# Mother_Board.net
KiCad netlist of a schematic drawn in EAGLE
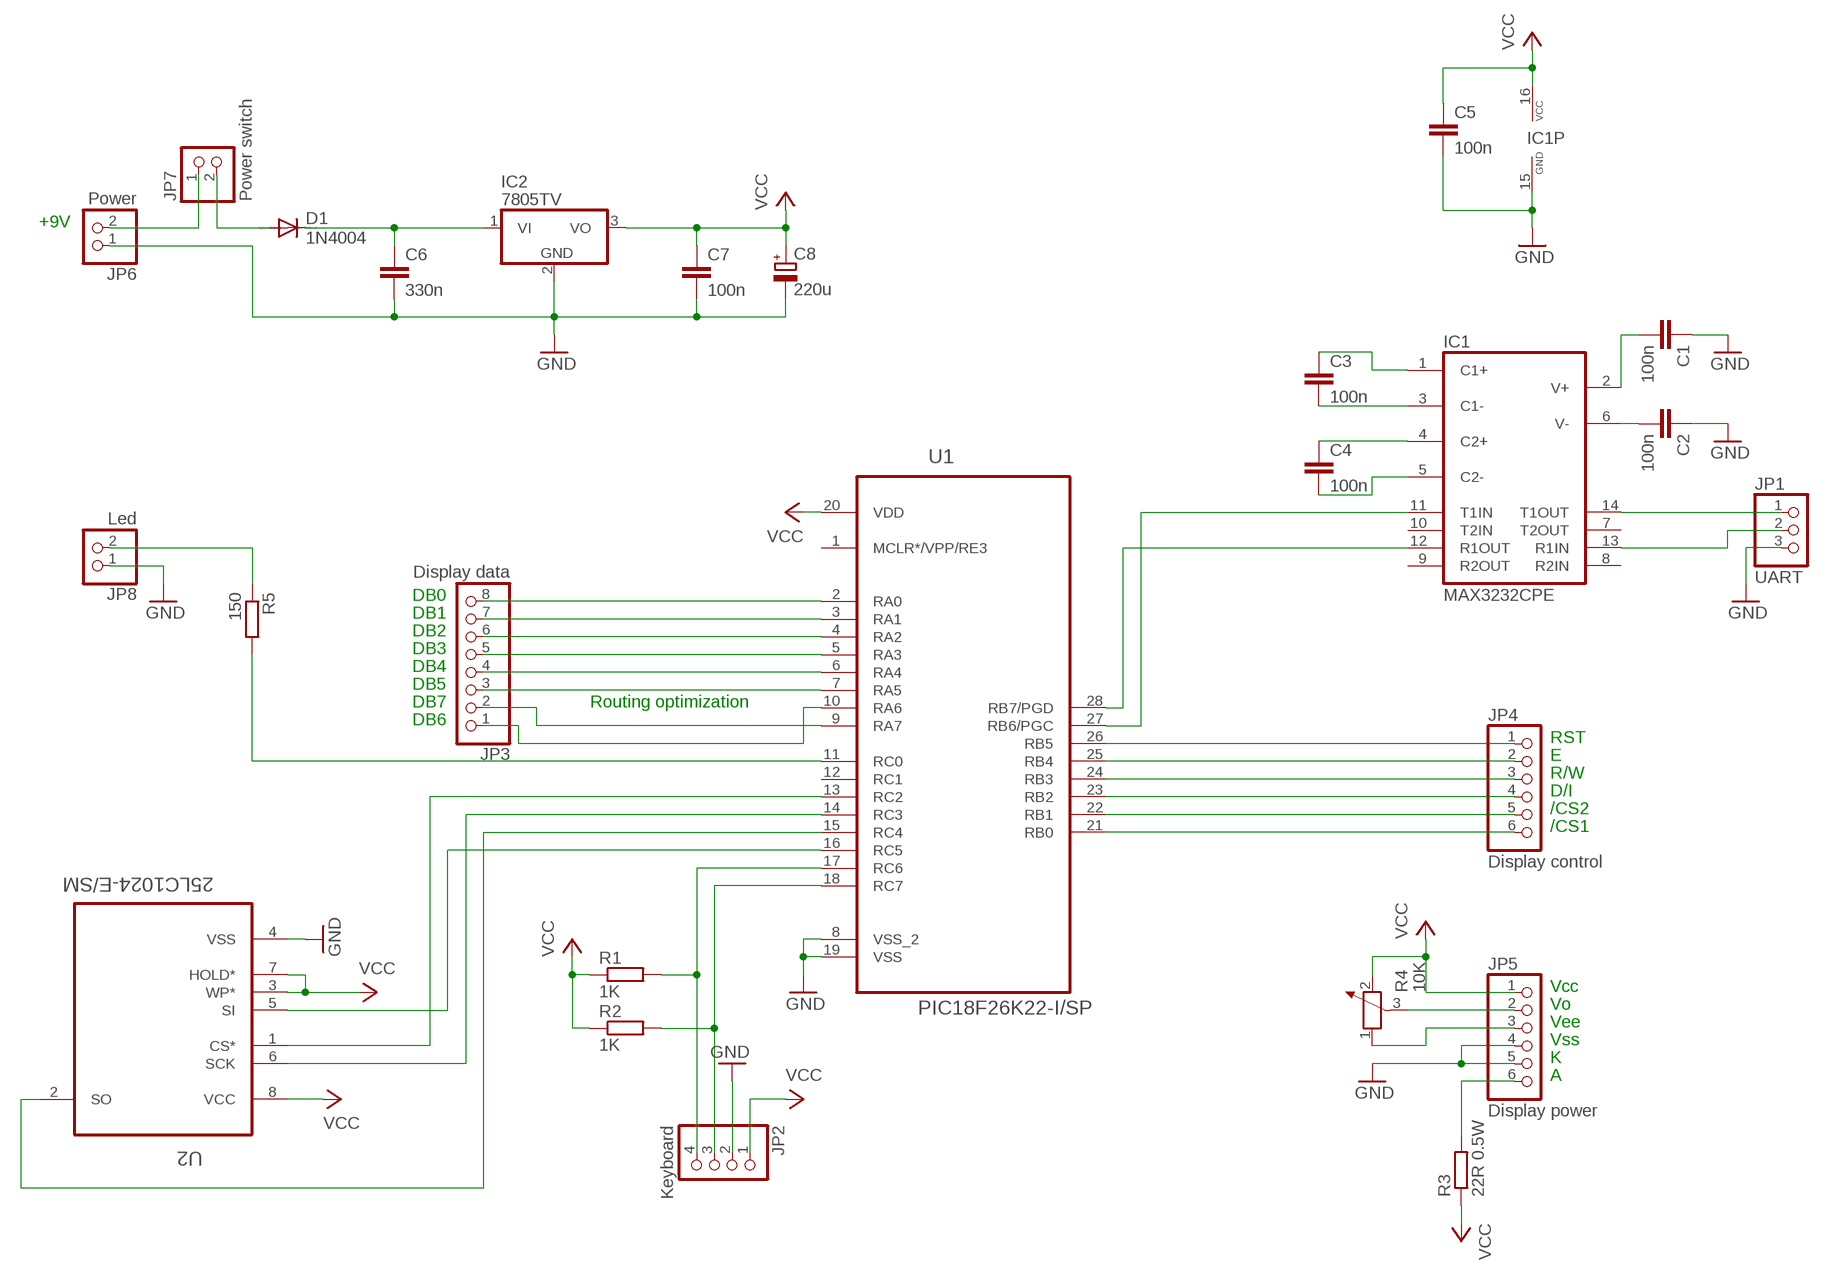
[diagram p0: schematic, sheet 1]

(export (version "E")
  (design (tool "Eeschema 10.0.6"))
  (components
    (comp (ref "C1")
      (value "100n")
      (footprint "eagle-import:C025-030X050")
      (libsource (lib "eagle-import") (part "C-EU025-030X050"))
    )
    (comp (ref "C2")
      (value "100n")
      (footprint "eagle-import:C025-030X050")
      (libsource (lib "eagle-import") (part "C-EU025-030X050"))
    )
    (comp (ref "C3")
      (value "100n")
      (footprint "eagle-import:C025-030X050")
      (libsource (lib "eagle-import") (part "C-EU025-030X050"))
    )
    (comp (ref "C4")
      (value "100n")
      (footprint "eagle-import:C025-030X050")
      (libsource (lib "eagle-import") (part "C-EU025-030X050"))
    )
    (comp (ref "C5")
      (value "100n")
      (footprint "eagle-import:C025-030X050")
      (libsource (lib "eagle-import") (part "C-EU025-030X050"))
    )
    (comp (ref "C6")
      (value "330n")
      (footprint "eagle-import:C025-050X050")
      (libsource (lib "eagle-import") (part "C-EU025-050X050"))
    )
    (comp (ref "C7")
      (value "100n")
      (footprint "eagle-import:C025-030X050")
      (libsource (lib "eagle-import") (part "C-EU025-030X050"))
    )
    (comp (ref "C8")
      (value "220u")
      (footprint "eagle-import:B45181A")
      (libsource (lib "eagle-import") (part "CPOL-EUB45181A"))
    )
    (comp (ref "D1")
      (value "1N4004")
      (footprint "eagle-import:DO41-10")
      (libsource (lib "eagle-import") (part "1N4004"))
    )
    (comp (ref "IC1")
      (value "MAX3232CPE")
      (footprint "eagle-import:DIL16")
      (fields (field (name "MF") "MAXIM") (field (name "MPN") "MAX3232CPE+"))
      (libsource (lib "eagle-import") (part "MAX3232PEC"))
    )
    (comp (ref "IC2")
      (value "7805TV")
      (footprint "eagle-import:TO220V")
      (libsource (lib "eagle-import") (part "78TV05"))
    )
    (comp (ref "JP1")
      (value "UART")
      (footprint "eagle-import:1X03")
      (libsource (lib "eagle-import") (part "PINHD-1X3"))
    )
    (comp (ref "JP2")
      (value "Keyboard")
      (footprint "eagle-import:1X04")
      (libsource (lib "eagle-import") (part "PINHD-1X4"))
    )
    (comp (ref "JP3")
      (value "Display data")
      (footprint "eagle-import:1X08")
      (libsource (lib "eagle-import") (part "PINHD-1X8"))
    )
    (comp (ref "JP4")
      (value "Display control")
      (footprint "eagle-import:1X06")
      (libsource (lib "eagle-import") (part "PINHD-1X6"))
    )
    (comp (ref "JP5")
      (value "Display power")
      (footprint "eagle-import:1X06")
      (libsource (lib "eagle-import") (part "PINHD-1X6"))
    )
    (comp (ref "JP6")
      (value "Power")
      (footprint "eagle-import:1X02")
      (libsource (lib "eagle-import") (part "PINHD-1X2"))
    )
    (comp (ref "JP7")
      (value "Power switch")
      (footprint "eagle-import:1X02")
      (libsource (lib "eagle-import") (part "PINHD-1X2"))
    )
    (comp (ref "JP8")
      (value "Led")
      (footprint "eagle-import:1X02")
      (libsource (lib "eagle-import") (part "PINHD-1X2"))
    )
    (comp (ref "R1")
      (value "1K")
      (footprint "eagle-import:0207_10")
      (libsource (lib "eagle-import") (part "R-EU_0207/10"))
    )
    (comp (ref "R2")
      (value "1K")
      (footprint "eagle-import:0207_10")
      (libsource (lib "eagle-import") (part "R-EU_0207/10"))
    )
    (comp (ref "R3")
      (value "22R 0.5W")
      (footprint "eagle-import:0207_10")
      (libsource (lib "eagle-import") (part "resistor_R-EU_0207/10"))
    )
    (comp (ref "R4")
      (value "10K")
      (footprint "eagle-import:PT-10S")
      (libsource (lib "eagle-import") (part "POTENTIOMETER_PT-10S"))
    )
    (comp (ref "R5")
      (value "150")
      (footprint "eagle-import:0207_10")
      (libsource (lib "eagle-import") (part "R-EU_0207/10"))
    )
    (comp (ref "U1")
      (value "PIC18F26K22-I/SP")
      (footprint "eagle-import:DIP254P762X508-28P")
      (libsource (lib "eagle-import") (part "PIC18F26K22-I/SP"))
    )
    (comp (ref "U2")
      (value "25LC1024-E/SM")
      (footprint "eagle-import:SOIC127P794X203-8N")
      (libsource (lib "eagle-import") (part "25LC1024-E/SM"))
    )
  )
  (nets
    (net (code "1") (name "GND") (class "Default")
      (node (ref "C1") (pin "1") (pinfunction "1_1") (pintype "passive"))
      (node (ref "C2") (pin "1") (pinfunction "1_1") (pintype "passive"))
      (node (ref "C5") (pin "2") (pinfunction "2_2") (pintype "passive"))
      (node (ref "C6") (pin "2") (pinfunction "2_2") (pintype "passive"))
      (node (ref "C7") (pin "2") (pinfunction "2_2") (pintype "passive"))
      (node (ref "C8") (pin "-") (pinfunction "-_-") (pintype "passive"))
      (node (ref "IC1") (pin "15") (pinfunction "GND_15") (pintype "power_in"))
      (node (ref "IC2") (pin "2") (pinfunction "GND_2") (pintype "passive"))
      (node (ref "JP1") (pin "3") (pinfunction "3_3") (pintype "passive"))
      (node (ref "JP2") (pin "2") (pinfunction "2_2") (pintype "passive"))
      (node (ref "JP5") (pin "4") (pinfunction "4_4") (pintype "passive"))
      (node (ref "JP5") (pin "5") (pinfunction "5_5") (pintype "passive"))
      (node (ref "JP6") (pin "1") (pinfunction "1_1") (pintype "passive"))
      (node (ref "JP8") (pin "1") (pinfunction "1_1") (pintype "passive"))
      (node (ref "U1") (pin "19") (pinfunction "VSS_19") (pintype "power_in"))
      (node (ref "U1") (pin "8") (pinfunction "VSS_2_8") (pintype "power_in"))
      (node (ref "U2") (pin "4") (pinfunction "VSS_4") (pintype "passive"))
    )
    (net (code "2") (name "Net-(D1-PadA)") (class "Default")
      (node (ref "D1") (pin "A") (pinfunction "A_A") (pintype "passive"))
      (node (ref "JP7") (pin "2") (pinfunction "2_2") (pintype "passive"))
    )
    (net (code "3") (name "Net-(IC1A-C1+)") (class "Default")
      (node (ref "C3") (pin "1") (pinfunction "1_1") (pintype "passive"))
      (node (ref "IC1") (pin "1") (pinfunction "C1+_1") (pintype "bidirectional"))
    )
    (net (code "4") (name "Net-(IC1A-C1-)") (class "Default")
      (node (ref "C3") (pin "2") (pinfunction "2_2") (pintype "passive"))
      (node (ref "IC1") (pin "3") (pinfunction "C1-_3") (pintype "bidirectional"))
    )
    (net (code "5") (name "Net-(IC1A-C2+)") (class "Default")
      (node (ref "C4") (pin "1") (pinfunction "1_1") (pintype "passive"))
      (node (ref "IC1") (pin "4") (pinfunction "C2+_4") (pintype "bidirectional"))
    )
    (net (code "6") (name "Net-(IC1A-C2-)") (class "Default")
      (node (ref "C4") (pin "2") (pinfunction "2_2") (pintype "passive"))
      (node (ref "IC1") (pin "5") (pinfunction "C2-_5") (pintype "bidirectional"))
    )
    (net (code "7") (name "Net-(IC1A-R1IN)") (class "Default")
      (node (ref "IC1") (pin "13") (pinfunction "R1IN_13") (pintype "input"))
      (node (ref "JP1") (pin "2") (pinfunction "2_2") (pintype "passive"))
    )
    (net (code "8") (name "Net-(IC1A-R1OUT)") (class "Default")
      (node (ref "IC1") (pin "12") (pinfunction "R1OUT_12") (pintype "output"))
      (node (ref "U1") (pin "28") (pinfunction "RB7/PGD_28") (pintype "bidirectional"))
    )
    (net (code "9") (name "Net-(IC1A-T1IN)") (class "Default")
      (node (ref "IC1") (pin "11") (pinfunction "T1IN_11") (pintype "input"))
      (node (ref "U1") (pin "27") (pinfunction "RB6/PGC_27") (pintype "bidirectional"))
    )
    (net (code "10") (name "Net-(IC1A-T1OUT)") (class "Default")
      (node (ref "IC1") (pin "14") (pinfunction "T1OUT_14") (pintype "output"))
      (node (ref "JP1") (pin "1") (pinfunction "1_1") (pintype "passive"))
    )
    (net (code "11") (name "Net-(IC1A-V+)") (class "Default")
      (node (ref "C1") (pin "2") (pinfunction "2_2") (pintype "passive"))
      (node (ref "IC1") (pin "2") (pinfunction "V+_2") (pintype "bidirectional"))
    )
    (net (code "12") (name "Net-(IC1A-V-)") (class "Default")
      (node (ref "C2") (pin "2") (pinfunction "2_2") (pintype "passive"))
      (node (ref "IC1") (pin "6") (pinfunction "V-_6") (pintype "bidirectional"))
    )
    (net (code "13") (name "Net-(IC2-VI)") (class "Default")
      (node (ref "C6") (pin "1") (pinfunction "1_1") (pintype "passive"))
      (node (ref "D1") (pin "C") (pinfunction "C_C") (pintype "passive"))
      (node (ref "IC2") (pin "1") (pinfunction "VI_1") (pintype "input"))
    )
    (net (code "14") (name "Net-(JP5-Pad2)") (class "Default")
      (node (ref "JP5") (pin "2") (pinfunction "2_2") (pintype "passive"))
      (node (ref "R4") (pin "3") (pinfunction "3_3") (pintype "passive"))
    )
    (net (code "15") (name "Net-(JP5-Pad3)") (class "Default")
      (node (ref "JP5") (pin "3") (pinfunction "3_3") (pintype "passive"))
      (node (ref "R4") (pin "1") (pinfunction "1_1") (pintype "passive"))
    )
    (net (code "16") (name "Net-(JP5-Pad6)") (class "Default")
      (node (ref "JP5") (pin "6") (pinfunction "6_6") (pintype "passive"))
      (node (ref "R3") (pin "2") (pinfunction "2_2") (pintype "passive"))
    )
    (net (code "17") (name "Net-(JP6-Pad2)") (class "Default")
      (node (ref "JP6") (pin "2") (pinfunction "2_2") (pintype "passive"))
      (node (ref "JP7") (pin "1") (pinfunction "1_1") (pintype "passive"))
    )
    (net (code "18") (name "Net-(JP8-Pad2)") (class "Default")
      (node (ref "JP8") (pin "2") (pinfunction "2_2") (pintype "passive"))
      (node (ref "R5") (pin "1") (pinfunction "1_1") (pintype "passive"))
    )
    (net (code "19") (name "Net-(U1-RA0)") (class "Default")
      (node (ref "JP3") (pin "8") (pinfunction "8_8") (pintype "passive"))
      (node (ref "U1") (pin "2") (pinfunction "RA0_2") (pintype "bidirectional"))
    )
    (net (code "20") (name "Net-(U1-RA1)") (class "Default")
      (node (ref "JP3") (pin "7") (pinfunction "7_7") (pintype "passive"))
      (node (ref "U1") (pin "3") (pinfunction "RA1_3") (pintype "bidirectional"))
    )
    (net (code "21") (name "Net-(U1-RA2)") (class "Default")
      (node (ref "JP3") (pin "6") (pinfunction "6_6") (pintype "passive"))
      (node (ref "U1") (pin "4") (pinfunction "RA2_4") (pintype "bidirectional"))
    )
    (net (code "22") (name "Net-(U1-RA3)") (class "Default")
      (node (ref "JP3") (pin "5") (pinfunction "5_5") (pintype "passive"))
      (node (ref "U1") (pin "5") (pinfunction "RA3_5") (pintype "bidirectional"))
    )
    (net (code "23") (name "Net-(U1-RA4)") (class "Default")
      (node (ref "JP3") (pin "4") (pinfunction "4_4") (pintype "passive"))
      (node (ref "U1") (pin "6") (pinfunction "RA4_6") (pintype "bidirectional"))
    )
    (net (code "24") (name "Net-(U1-RA5)") (class "Default")
      (node (ref "JP3") (pin "3") (pinfunction "3_3") (pintype "passive"))
      (node (ref "U1") (pin "7") (pinfunction "RA5_7") (pintype "bidirectional"))
    )
    (net (code "25") (name "Net-(U1-RA6)") (class "Default")
      (node (ref "JP3") (pin "1") (pinfunction "1_1") (pintype "passive"))
      (node (ref "U1") (pin "10") (pinfunction "RA6_10") (pintype "bidirectional"))
    )
    (net (code "26") (name "Net-(U1-RA7)") (class "Default")
      (node (ref "JP3") (pin "2") (pinfunction "2_2") (pintype "passive"))
      (node (ref "U1") (pin "9") (pinfunction "RA7_9") (pintype "bidirectional"))
    )
    (net (code "27") (name "Net-(U1-RB0)") (class "Default")
      (node (ref "JP4") (pin "6") (pinfunction "6_6") (pintype "passive"))
      (node (ref "U1") (pin "21") (pinfunction "RB0_21") (pintype "bidirectional"))
    )
    (net (code "28") (name "Net-(U1-RB1)") (class "Default")
      (node (ref "JP4") (pin "5") (pinfunction "5_5") (pintype "passive"))
      (node (ref "U1") (pin "22") (pinfunction "RB1_22") (pintype "bidirectional"))
    )
    (net (code "29") (name "Net-(U1-RB2)") (class "Default")
      (node (ref "JP4") (pin "4") (pinfunction "4_4") (pintype "passive"))
      (node (ref "U1") (pin "23") (pinfunction "RB2_23") (pintype "bidirectional"))
    )
    (net (code "30") (name "Net-(U1-RB3)") (class "Default")
      (node (ref "JP4") (pin "3") (pinfunction "3_3") (pintype "passive"))
      (node (ref "U1") (pin "24") (pinfunction "RB3_24") (pintype "bidirectional"))
    )
    (net (code "31") (name "Net-(U1-RB4)") (class "Default")
      (node (ref "JP4") (pin "2") (pinfunction "2_2") (pintype "passive"))
      (node (ref "U1") (pin "25") (pinfunction "RB4_25") (pintype "bidirectional"))
    )
    (net (code "32") (name "Net-(U1-RB5)") (class "Default")
      (node (ref "JP4") (pin "1") (pinfunction "1_1") (pintype "passive"))
      (node (ref "U1") (pin "26") (pinfunction "RB5_26") (pintype "bidirectional"))
    )
    (net (code "33") (name "Net-(U1-RC0)") (class "Default")
      (node (ref "R5") (pin "2") (pinfunction "2_2") (pintype "passive"))
      (node (ref "U1") (pin "11") (pinfunction "RC0_11") (pintype "bidirectional"))
    )
    (net (code "34") (name "Net-(U1-RC2)") (class "Default")
      (node (ref "U1") (pin "13") (pinfunction "RC2_13") (pintype "bidirectional"))
      (node (ref "U2") (pin "1") (pinfunction "CS*_1") (pintype "input"))
    )
    (net (code "35") (name "Net-(U1-RC3)") (class "Default")
      (node (ref "U1") (pin "14") (pinfunction "RC3_14") (pintype "bidirectional"))
      (node (ref "U2") (pin "6") (pinfunction "SCK_6") (pintype "input"))
    )
    (net (code "36") (name "Net-(U1-RC4)") (class "Default")
      (node (ref "U1") (pin "15") (pinfunction "RC4_15") (pintype "bidirectional"))
      (node (ref "U2") (pin "2") (pinfunction "SO_2") (pintype "output"))
    )
    (net (code "37") (name "Net-(U1-RC5)") (class "Default")
      (node (ref "U1") (pin "16") (pinfunction "RC5_16") (pintype "bidirectional"))
      (node (ref "U2") (pin "5") (pinfunction "SI_5") (pintype "input"))
    )
    (net (code "38") (name "Net-(U1-RC6)") (class "Default")
      (node (ref "JP2") (pin "4") (pinfunction "4_4") (pintype "passive"))
      (node (ref "R1") (pin "2") (pinfunction "2_2") (pintype "passive"))
      (node (ref "U1") (pin "17") (pinfunction "RC6_17") (pintype "bidirectional"))
    )
    (net (code "39") (name "Net-(U1-RC7)") (class "Default")
      (node (ref "JP2") (pin "3") (pinfunction "3_3") (pintype "passive"))
      (node (ref "R2") (pin "2") (pinfunction "2_2") (pintype "passive"))
      (node (ref "U1") (pin "18") (pinfunction "RC7_18") (pintype "bidirectional"))
    )
    (net (code "40") (name "VCC") (class "Default")
      (node (ref "C5") (pin "1") (pinfunction "1_1") (pintype "passive"))
      (node (ref "C7") (pin "1") (pinfunction "1_1") (pintype "passive"))
      (node (ref "C8") (pin "+") (pinfunction "+_+") (pintype "passive"))
      (node (ref "IC1") (pin "16") (pinfunction "VCC_16") (pintype "power_in"))
      (node (ref "IC2") (pin "3") (pinfunction "VO_3") (pintype "passive"))
      (node (ref "JP2") (pin "1") (pinfunction "1_1") (pintype "passive"))
      (node (ref "JP5") (pin "1") (pinfunction "1_1") (pintype "passive"))
      (node (ref "R1") (pin "1") (pinfunction "1_1") (pintype "passive"))
      (node (ref "R2") (pin "1") (pinfunction "1_1") (pintype "passive"))
      (node (ref "R3") (pin "1") (pinfunction "1_1") (pintype "passive"))
      (node (ref "R4") (pin "2") (pinfunction "2_2") (pintype "passive"))
      (node (ref "U1") (pin "20") (pinfunction "VDD_20") (pintype "power_in"))
      (node (ref "U2") (pin "3") (pinfunction "WP*_3") (pintype "input"))
      (node (ref "U2") (pin "7") (pinfunction "HOLD*_7") (pintype "input"))
      (node (ref "U2") (pin "8") (pinfunction "VCC_8") (pintype "power_in"))
    )
    (net (code "41") (name "unconnected-(IC1A-R2IN-Pad8)") (class "Default")
      (node (ref "IC1") (pin "8") (pinfunction "R2IN_8") (pintype "input"))
    )
    (net (code "42") (name "unconnected-(IC1A-R2OUT-Pad9)") (class "Default")
      (node (ref "IC1") (pin "9") (pinfunction "R2OUT_9") (pintype "output"))
    )
    (net (code "43") (name "unconnected-(IC1A-T2IN-Pad10)") (class "Default")
      (node (ref "IC1") (pin "10") (pinfunction "T2IN_10") (pintype "input"))
    )
    (net (code "44") (name "unconnected-(IC1A-T2OUT-Pad7)") (class "Default")
      (node (ref "IC1") (pin "7") (pinfunction "T2OUT_7") (pintype "output"))
    )
    (net (code "45") (name "unconnected-(U1-MCLR*{slash}VPP{slash}RE3-Pad1)") (class "Default")
      (node (ref "U1") (pin "1") (pinfunction "MCLR*/VPP/RE3_1") (pintype "input"))
    )
    (net (code "46") (name "unconnected-(U1-RC1-Pad12)") (class "Default")
      (node (ref "U1") (pin "12") (pinfunction "RC1_12") (pintype "bidirectional"))
    )
  )
)
